# Connectors.net
KiCad netlist of a schematic drawn in Altium Designer
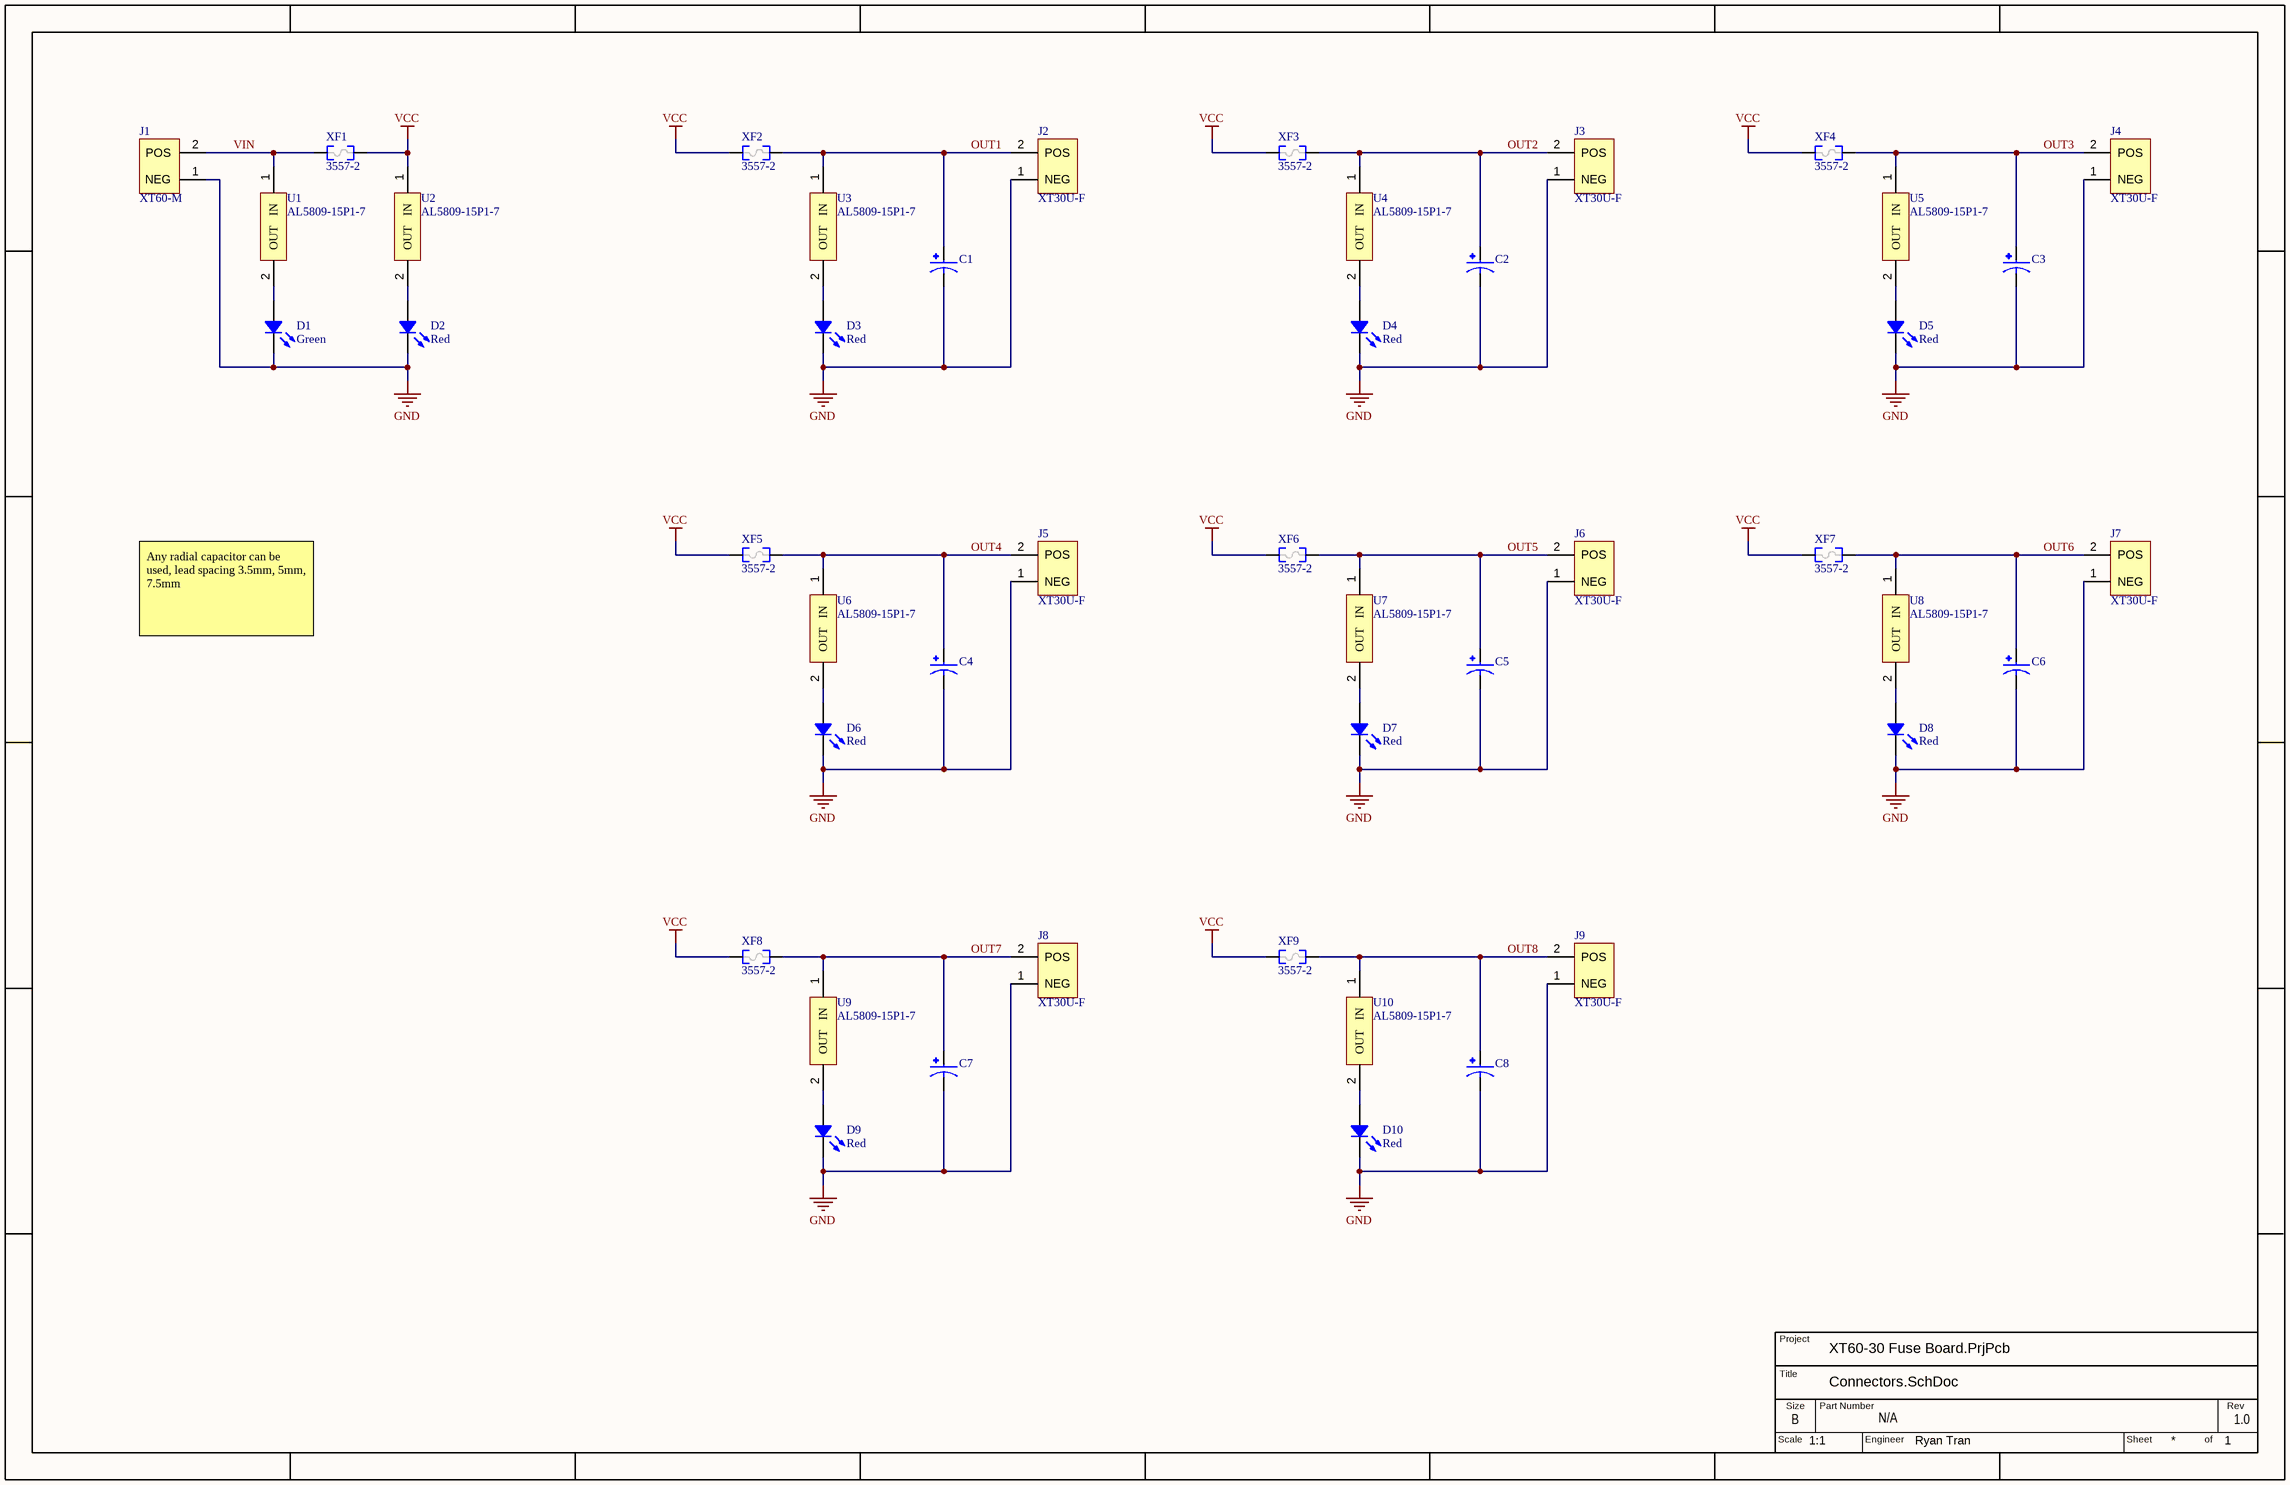
[diagram p0: Connectors.SchDoc]

(export (version "E")
  (design (tool "Eeschema 10.0.6"))
  (components
    (comp (ref "C1")
      (value "Capacitor Generic")
      (footprint "RADIAL_CAP_10mm")
      (description "Cap Radial Aluminum Cylindrical Can 3.5mm, 5mm, 7.5mm")
      (fields (field (name "MF") "Panasonic") (field (name "MP") "ECA-2WHG220"))
      (libsource (lib "XT60-30_Fuse_Board_Symbols") (part "Capacitor Generic"))
    )
    (comp (ref "C2")
      (value "Capacitor Generic")
      (footprint "RADIAL_CAP_10mm")
      (description "Cap Radial Aluminum Cylindrical Can 3.5mm, 5mm, 7.5mm")
      (fields (field (name "MF") "Panasonic") (field (name "MP") "ECA-2WHG220"))
      (libsource (lib "XT60-30_Fuse_Board_Symbols") (part "Capacitor Generic"))
    )
    (comp (ref "C3")
      (value "Capacitor Generic")
      (footprint "RADIAL_CAP_10mm")
      (description "Cap Radial Aluminum Cylindrical Can 3.5mm, 5mm, 7.5mm")
      (fields (field (name "MF") "Panasonic") (field (name "MP") "ECA-2WHG220"))
      (libsource (lib "XT60-30_Fuse_Board_Symbols") (part "Capacitor Generic"))
    )
    (comp (ref "C4")
      (value "Capacitor Generic")
      (footprint "RADIAL_CAP_10mm")
      (description "Cap Radial Aluminum Cylindrical Can 3.5mm, 5mm, 7.5mm")
      (fields (field (name "MF") "Panasonic") (field (name "MP") "ECA-2WHG220"))
      (libsource (lib "XT60-30_Fuse_Board_Symbols") (part "Capacitor Generic"))
    )
    (comp (ref "C5")
      (value "Capacitor Generic")
      (footprint "RADIAL_CAP_10mm")
      (description "Cap Radial Aluminum Cylindrical Can 3.5mm, 5mm, 7.5mm")
      (fields (field (name "MF") "Panasonic") (field (name "MP") "ECA-2WHG220"))
      (libsource (lib "XT60-30_Fuse_Board_Symbols") (part "Capacitor Generic"))
    )
    (comp (ref "C6")
      (value "Capacitor Generic")
      (footprint "RADIAL_CAP_10mm")
      (description "Cap Radial Aluminum Cylindrical Can 3.5mm, 5mm, 7.5mm")
      (fields (field (name "MF") "Panasonic") (field (name "MP") "ECA-2WHG220"))
      (libsource (lib "XT60-30_Fuse_Board_Symbols") (part "Capacitor Generic"))
    )
    (comp (ref "C7")
      (value "Capacitor Generic")
      (footprint "RADIAL_CAP_10mm")
      (description "Cap Radial Aluminum Cylindrical Can 3.5mm, 5mm, 7.5mm")
      (fields (field (name "MF") "Panasonic") (field (name "MP") "ECA-2WHG220"))
      (libsource (lib "XT60-30_Fuse_Board_Symbols") (part "Capacitor Generic"))
    )
    (comp (ref "C8")
      (value "Capacitor Generic")
      (footprint "RADIAL_CAP_10mm")
      (description "Cap Radial Aluminum Cylindrical Can 3.5mm, 5mm, 7.5mm")
      (fields (field (name "MF") "Panasonic") (field (name "MP") "ECA-2WHG220"))
      (libsource (lib "XT60-30_Fuse_Board_Symbols") (part "Capacitor Generic"))
    )
    (comp (ref "D1")
      (value "Green")
      (footprint "LED 0603_1608 GREEN")
      (description "LED GREEN CLEAR CHIP SMD")
      (fields (field (name "PART NUMBER") "LTST-C193TGKT-5A") (field (name "MANUFACTURER") "Lite-On Inc."))
      (libsource (lib "Celestial Altium Library - altium_library") (part "LED"))
    )
    (comp (ref "D2")
      (value "Red")
      (footprint "LED 0603_1608 RED")
      (description "LED RED CLEAR 2SMD")
      (fields
        (field (name "PART NUMBER") "19-217/R6C-AL1M2VY/3T")
        (field (name "MANUFACTURER") "Everlight Electronics Co Ltd")
      )
      (libsource (lib "Celestial Altium Library - altium_library") (part "LED"))
    )
    (comp (ref "D3")
      (value "Red")
      (footprint "LED 0603_1608 RED")
      (description "LED RED CLEAR 2SMD")
      (fields
        (field (name "PART NUMBER") "19-217/R6C-AL1M2VY/3T")
        (field (name "MANUFACTURER") "Everlight Electronics Co Ltd")
      )
      (libsource (lib "Celestial Altium Library - altium_library") (part "LED"))
    )
    (comp (ref "D4")
      (value "Red")
      (footprint "LED 0603_1608 RED")
      (description "LED RED CLEAR 2SMD")
      (fields
        (field (name "PART NUMBER") "19-217/R6C-AL1M2VY/3T")
        (field (name "MANUFACTURER") "Everlight Electronics Co Ltd")
      )
      (libsource (lib "Celestial Altium Library - altium_library") (part "LED"))
    )
    (comp (ref "D5")
      (value "Red")
      (footprint "LED 0603_1608 RED")
      (description "LED RED CLEAR 2SMD")
      (fields
        (field (name "PART NUMBER") "19-217/R6C-AL1M2VY/3T")
        (field (name "MANUFACTURER") "Everlight Electronics Co Ltd")
      )
      (libsource (lib "Celestial Altium Library - altium_library") (part "LED"))
    )
    (comp (ref "D6")
      (value "Red")
      (footprint "LED 0603_1608 RED")
      (description "LED RED CLEAR 2SMD")
      (fields
        (field (name "PART NUMBER") "19-217/R6C-AL1M2VY/3T")
        (field (name "MANUFACTURER") "Everlight Electronics Co Ltd")
      )
      (libsource (lib "Celestial Altium Library - altium_library") (part "LED"))
    )
    (comp (ref "D7")
      (value "Red")
      (footprint "LED 0603_1608 RED")
      (description "LED RED CLEAR 2SMD")
      (fields
        (field (name "PART NUMBER") "19-217/R6C-AL1M2VY/3T")
        (field (name "MANUFACTURER") "Everlight Electronics Co Ltd")
      )
      (libsource (lib "Celestial Altium Library - altium_library") (part "LED"))
    )
    (comp (ref "D8")
      (value "Red")
      (footprint "LED 0603_1608 RED")
      (description "LED RED CLEAR 2SMD")
      (fields
        (field (name "PART NUMBER") "19-217/R6C-AL1M2VY/3T")
        (field (name "MANUFACTURER") "Everlight Electronics Co Ltd")
      )
      (libsource (lib "Celestial Altium Library - altium_library") (part "LED"))
    )
    (comp (ref "D9")
      (value "Red")
      (footprint "LED 0603_1608 RED")
      (description "LED RED CLEAR 2SMD")
      (fields
        (field (name "PART NUMBER") "19-217/R6C-AL1M2VY/3T")
        (field (name "MANUFACTURER") "Everlight Electronics Co Ltd")
      )
      (libsource (lib "Celestial Altium Library - altium_library") (part "LED"))
    )
    (comp (ref "D10")
      (value "Red")
      (footprint "LED 0603_1608 RED")
      (description "LED RED CLEAR 2SMD")
      (fields
        (field (name "PART NUMBER") "19-217/R6C-AL1M2VY/3T")
        (field (name "MANUFACTURER") "Everlight Electronics Co Ltd")
      )
      (libsource (lib "Celestial Altium Library - altium_library") (part "LED"))
    )
    (comp (ref "J1")
      (value "XT60-M")
      (footprint "AMASS_XT60-M")
      (description "Plug; DC supply; XT60; male; PIN: 2; for cable; soldered; 30A; 500V")
      (fields (field (name "MF") "AMASS"))
      (libsource (lib "XT60-30_Fuse_Board_Symbols") (part "XT60-M"))
    )
    (comp (ref "J2")
      (value "XT30U-F")
      (footprint "AMASS_XT30-M")
      (description "Plug; DC supply; XT30; female; PIN: 2; for cable; soldering; 15A")
      (fields (field (name "MP") "XT60-M") (field (name "MF") "AMASS"))
      (libsource (lib "XT60-30_Fuse_Board_Symbols") (part "XT30U-F"))
    )
    (comp (ref "J3")
      (value "XT30U-F")
      (footprint "AMASS_XT30-M")
      (description "Plug; DC supply; XT30; female; PIN: 2; for cable; soldering; 15A")
      (fields (field (name "MP") "XT60-M") (field (name "MF") "AMASS"))
      (libsource (lib "XT60-30_Fuse_Board_Symbols") (part "XT30U-F"))
    )
    (comp (ref "J4")
      (value "XT30U-F")
      (footprint "AMASS_XT30-M")
      (description "Plug; DC supply; XT30; female; PIN: 2; for cable; soldering; 15A")
      (fields (field (name "MP") "XT60-M") (field (name "MF") "AMASS"))
      (libsource (lib "XT60-30_Fuse_Board_Symbols") (part "XT30U-F"))
    )
    (comp (ref "J5")
      (value "XT30U-F")
      (footprint "AMASS_XT30-M")
      (description "Plug; DC supply; XT30; female; PIN: 2; for cable; soldering; 15A")
      (fields (field (name "MP") "XT60-M") (field (name "MF") "AMASS"))
      (libsource (lib "XT60-30_Fuse_Board_Symbols") (part "XT30U-F"))
    )
    (comp (ref "J6")
      (value "XT30U-F")
      (footprint "AMASS_XT30-M")
      (description "Plug; DC supply; XT30; female; PIN: 2; for cable; soldering; 15A")
      (fields (field (name "MP") "XT60-M") (field (name "MF") "AMASS"))
      (libsource (lib "XT60-30_Fuse_Board_Symbols") (part "XT30U-F"))
    )
    (comp (ref "J7")
      (value "XT30U-F")
      (footprint "AMASS_XT30-M")
      (description "Plug; DC supply; XT30; female; PIN: 2; for cable; soldering; 15A")
      (fields (field (name "MP") "XT60-M") (field (name "MF") "AMASS"))
      (libsource (lib "XT60-30_Fuse_Board_Symbols") (part "XT30U-F"))
    )
    (comp (ref "J8")
      (value "XT30U-F")
      (footprint "AMASS_XT30-M")
      (description "Plug; DC supply; XT30; female; PIN: 2; for cable; soldering; 15A")
      (fields (field (name "MP") "XT60-M") (field (name "MF") "AMASS"))
      (libsource (lib "XT60-30_Fuse_Board_Symbols") (part "XT30U-F"))
    )
    (comp (ref "J9")
      (value "XT30U-F")
      (footprint "AMASS_XT30-M")
      (description "Plug; DC supply; XT30; female; PIN: 2; for cable; soldering; 15A")
      (fields (field (name "MP") "XT60-M") (field (name "MF") "AMASS"))
      (libsource (lib "XT60-30_Fuse_Board_Symbols") (part "XT30U-F"))
    )
    (comp (ref "U1")
      (value "AL5809-15P1-7")
      (footprint "DIOD-POWERDI123-2_B_V")
      (description "Constant Current LED Driver, 2.5 to 60 V, -40 to 125 degC, 2-Pin SMD, RoHS, Tape and Reel")
      (libsource (lib "Altium Content Vault") (part "DIOD-AL5809-2"))
    )
    (comp (ref "U2")
      (value "AL5809-15P1-7")
      (footprint "DIOD-POWERDI123-2_B_V")
      (description "Constant Current LED Driver, 2.5 to 60 V, -40 to 125 degC, 2-Pin SMD, RoHS, Tape and Reel")
      (libsource (lib "Altium Content Vault") (part "DIOD-AL5809-2"))
    )
    (comp (ref "U3")
      (value "AL5809-15P1-7")
      (footprint "DIOD-POWERDI123-2_B_V")
      (description "Constant Current LED Driver, 2.5 to 60 V, -40 to 125 degC, 2-Pin SMD, RoHS, Tape and Reel")
      (libsource (lib "Altium Content Vault") (part "DIOD-AL5809-2"))
    )
    (comp (ref "U4")
      (value "AL5809-15P1-7")
      (footprint "DIOD-POWERDI123-2_B_V")
      (description "Constant Current LED Driver, 2.5 to 60 V, -40 to 125 degC, 2-Pin SMD, RoHS, Tape and Reel")
      (libsource (lib "Altium Content Vault") (part "DIOD-AL5809-2"))
    )
    (comp (ref "U5")
      (value "AL5809-15P1-7")
      (footprint "DIOD-POWERDI123-2_B_V")
      (description "Constant Current LED Driver, 2.5 to 60 V, -40 to 125 degC, 2-Pin SMD, RoHS, Tape and Reel")
      (libsource (lib "Altium Content Vault") (part "DIOD-AL5809-2"))
    )
    (comp (ref "U6")
      (value "AL5809-15P1-7")
      (footprint "DIOD-POWERDI123-2_B_V")
      (description "Constant Current LED Driver, 2.5 to 60 V, -40 to 125 degC, 2-Pin SMD, RoHS, Tape and Reel")
      (libsource (lib "Altium Content Vault") (part "DIOD-AL5809-2"))
    )
    (comp (ref "U7")
      (value "AL5809-15P1-7")
      (footprint "DIOD-POWERDI123-2_B_V")
      (description "Constant Current LED Driver, 2.5 to 60 V, -40 to 125 degC, 2-Pin SMD, RoHS, Tape and Reel")
      (libsource (lib "Altium Content Vault") (part "DIOD-AL5809-2"))
    )
    (comp (ref "U8")
      (value "AL5809-15P1-7")
      (footprint "DIOD-POWERDI123-2_B_V")
      (description "Constant Current LED Driver, 2.5 to 60 V, -40 to 125 degC, 2-Pin SMD, RoHS, Tape and Reel")
      (libsource (lib "Altium Content Vault") (part "DIOD-AL5809-2"))
    )
    (comp (ref "U9")
      (value "AL5809-15P1-7")
      (footprint "DIOD-POWERDI123-2_B_V")
      (description "Constant Current LED Driver, 2.5 to 60 V, -40 to 125 degC, 2-Pin SMD, RoHS, Tape and Reel")
      (libsource (lib "Altium Content Vault") (part "DIOD-AL5809-2"))
    )
    (comp (ref "U10")
      (value "AL5809-15P1-7")
      (footprint "DIOD-POWERDI123-2_B_V")
      (description "Constant Current LED Driver, 2.5 to 60 V, -40 to 125 degC, 2-Pin SMD, RoHS, Tape and Reel")
      (libsource (lib "Altium Content Vault") (part "DIOD-AL5809-2"))
    )
    (comp (ref "XF1")
      (value "3557-2")
      (footprint "FUSE_3557-2")
      (description "Fuse Block 30A 500V 1 Circuit Blade Through Hole")
      (fields (field (name "MF") "Keystone Electronics"))
      (libsource (lib "XT60-30_Fuse_Board_Symbols") (part "3557-2"))
    )
    (comp (ref "XF2")
      (value "3557-2")
      (footprint "FUSE_3557-2")
      (description "Fuse Block 30A 500V 1 Circuit Blade Through Hole")
      (fields (field (name "MF") "Keystone Electronics"))
      (libsource (lib "XT60-30_Fuse_Board_Symbols") (part "3557-2"))
    )
    (comp (ref "XF3")
      (value "3557-2")
      (footprint "FUSE_3557-2")
      (description "Fuse Block 30A 500V 1 Circuit Blade Through Hole")
      (fields (field (name "MF") "Keystone Electronics"))
      (libsource (lib "XT60-30_Fuse_Board_Symbols") (part "3557-2"))
    )
    (comp (ref "XF4")
      (value "3557-2")
      (footprint "FUSE_3557-2")
      (description "Fuse Block 30A 500V 1 Circuit Blade Through Hole")
      (fields (field (name "MF") "Keystone Electronics"))
      (libsource (lib "XT60-30_Fuse_Board_Symbols") (part "3557-2"))
    )
    (comp (ref "XF5")
      (value "3557-2")
      (footprint "FUSE_3557-2")
      (description "Fuse Block 30A 500V 1 Circuit Blade Through Hole")
      (fields (field (name "MF") "Keystone Electronics"))
      (libsource (lib "XT60-30_Fuse_Board_Symbols") (part "3557-2"))
    )
    (comp (ref "XF6")
      (value "3557-2")
      (footprint "FUSE_3557-2")
      (description "Fuse Block 30A 500V 1 Circuit Blade Through Hole")
      (fields (field (name "MF") "Keystone Electronics"))
      (libsource (lib "XT60-30_Fuse_Board_Symbols") (part "3557-2"))
    )
    (comp (ref "XF7")
      (value "3557-2")
      (footprint "FUSE_3557-2")
      (description "Fuse Block 30A 500V 1 Circuit Blade Through Hole")
      (fields (field (name "MF") "Keystone Electronics"))
      (libsource (lib "XT60-30_Fuse_Board_Symbols") (part "3557-2"))
    )
    (comp (ref "XF8")
      (value "3557-2")
      (footprint "FUSE_3557-2")
      (description "Fuse Block 30A 500V 1 Circuit Blade Through Hole")
      (fields (field (name "MF") "Keystone Electronics"))
      (libsource (lib "XT60-30_Fuse_Board_Symbols") (part "3557-2"))
    )
    (comp (ref "XF9")
      (value "3557-2")
      (footprint "FUSE_3557-2")
      (description "Fuse Block 30A 500V 1 Circuit Blade Through Hole")
      (fields (field (name "MF") "Keystone Electronics"))
      (libsource (lib "XT60-30_Fuse_Board_Symbols") (part "3557-2"))
    )
  )
  (nets
    (net (code "1") (name "/OUT1") (class "Default")
      (node (ref "C1") (pin "2") (pinfunction "2_2") (pintype "passive"))
      (node (ref "J2") (pin "2") (pinfunction "POS_2") (pintype "passive"))
      (node (ref "U3") (pin "1") (pinfunction "IN_1") (pintype "passive"))
      (node (ref "XF2") (pin "2") (pinfunction "2_2") (pintype "passive"))
    )
    (net (code "2") (name "/OUT2") (class "Default")
      (node (ref "C2") (pin "2") (pinfunction "2_2") (pintype "passive"))
      (node (ref "J3") (pin "2") (pinfunction "POS_2") (pintype "passive"))
      (node (ref "U4") (pin "1") (pinfunction "IN_1") (pintype "passive"))
      (node (ref "XF3") (pin "2") (pinfunction "2_2") (pintype "passive"))
    )
    (net (code "3") (name "/OUT3") (class "Default")
      (node (ref "C3") (pin "2") (pinfunction "2_2") (pintype "passive"))
      (node (ref "J4") (pin "2") (pinfunction "POS_2") (pintype "passive"))
      (node (ref "U5") (pin "1") (pinfunction "IN_1") (pintype "passive"))
      (node (ref "XF4") (pin "2") (pinfunction "2_2") (pintype "passive"))
    )
    (net (code "4") (name "/OUT4") (class "Default")
      (node (ref "C4") (pin "2") (pinfunction "2_2") (pintype "passive"))
      (node (ref "J5") (pin "2") (pinfunction "POS_2") (pintype "passive"))
      (node (ref "U6") (pin "1") (pinfunction "IN_1") (pintype "passive"))
      (node (ref "XF5") (pin "2") (pinfunction "2_2") (pintype "passive"))
    )
    (net (code "5") (name "/OUT5") (class "Default")
      (node (ref "C5") (pin "2") (pinfunction "2_2") (pintype "passive"))
      (node (ref "J6") (pin "2") (pinfunction "POS_2") (pintype "passive"))
      (node (ref "U7") (pin "1") (pinfunction "IN_1") (pintype "passive"))
      (node (ref "XF6") (pin "2") (pinfunction "2_2") (pintype "passive"))
    )
    (net (code "6") (name "/OUT6") (class "Default")
      (node (ref "C6") (pin "2") (pinfunction "2_2") (pintype "passive"))
      (node (ref "J7") (pin "2") (pinfunction "POS_2") (pintype "passive"))
      (node (ref "U8") (pin "1") (pinfunction "IN_1") (pintype "passive"))
      (node (ref "XF7") (pin "2") (pinfunction "2_2") (pintype "passive"))
    )
    (net (code "7") (name "/OUT7") (class "Default")
      (node (ref "C7") (pin "2") (pinfunction "2_2") (pintype "passive"))
      (node (ref "J8") (pin "2") (pinfunction "POS_2") (pintype "passive"))
      (node (ref "U9") (pin "1") (pinfunction "IN_1") (pintype "passive"))
      (node (ref "XF8") (pin "2") (pinfunction "2_2") (pintype "passive"))
    )
    (net (code "8") (name "/OUT8") (class "Default")
      (node (ref "C8") (pin "2") (pinfunction "2_2") (pintype "passive"))
      (node (ref "J9") (pin "2") (pinfunction "POS_2") (pintype "passive"))
      (node (ref "U10") (pin "1") (pinfunction "IN_1") (pintype "passive"))
      (node (ref "XF9") (pin "2") (pinfunction "2_2") (pintype "passive"))
    )
    (net (code "9") (name "/VIN") (class "Default")
      (node (ref "J1") (pin "2") (pinfunction "POS_2") (pintype "passive"))
      (node (ref "U1") (pin "1") (pinfunction "IN_1") (pintype "passive"))
      (node (ref "XF1") (pin "1") (pinfunction "1_1") (pintype "passive"))
    )
    (net (code "10") (name "GND") (class "Default")
      (node (ref "C1") (pin "1") (pinfunction "1_1") (pintype "passive"))
      (node (ref "C2") (pin "1") (pinfunction "1_1") (pintype "passive"))
      (node (ref "C3") (pin "1") (pinfunction "1_1") (pintype "passive"))
      (node (ref "C4") (pin "1") (pinfunction "1_1") (pintype "passive"))
      (node (ref "C5") (pin "1") (pinfunction "1_1") (pintype "passive"))
      (node (ref "C6") (pin "1") (pinfunction "1_1") (pintype "passive"))
      (node (ref "C7") (pin "1") (pinfunction "1_1") (pintype "passive"))
      (node (ref "C8") (pin "1") (pinfunction "1_1") (pintype "passive"))
      (node (ref "D1") (pin "2") (pinfunction "2_2") (pintype "passive"))
      (node (ref "D10") (pin "2") (pinfunction "2_2") (pintype "passive"))
      (node (ref "D2") (pin "2") (pinfunction "2_2") (pintype "passive"))
      (node (ref "D3") (pin "2") (pinfunction "2_2") (pintype "passive"))
      (node (ref "D4") (pin "2") (pinfunction "2_2") (pintype "passive"))
      (node (ref "D5") (pin "2") (pinfunction "2_2") (pintype "passive"))
      (node (ref "D6") (pin "2") (pinfunction "2_2") (pintype "passive"))
      (node (ref "D7") (pin "2") (pinfunction "2_2") (pintype "passive"))
      (node (ref "D8") (pin "2") (pinfunction "2_2") (pintype "passive"))
      (node (ref "D9") (pin "2") (pinfunction "2_2") (pintype "passive"))
      (node (ref "J1") (pin "1") (pinfunction "NEG_1") (pintype "passive"))
      (node (ref "J2") (pin "1") (pinfunction "NEG_1") (pintype "passive"))
      (node (ref "J3") (pin "1") (pinfunction "NEG_1") (pintype "passive"))
      (node (ref "J4") (pin "1") (pinfunction "NEG_1") (pintype "passive"))
      (node (ref "J5") (pin "1") (pinfunction "NEG_1") (pintype "passive"))
      (node (ref "J6") (pin "1") (pinfunction "NEG_1") (pintype "passive"))
      (node (ref "J7") (pin "1") (pinfunction "NEG_1") (pintype "passive"))
      (node (ref "J8") (pin "1") (pinfunction "NEG_1") (pintype "passive"))
      (node (ref "J9") (pin "1") (pinfunction "NEG_1") (pintype "passive"))
    )
    (net (code "11") (name "Net-(U1-OUT)") (class "Default")
      (node (ref "D1") (pin "1") (pinfunction "1_1") (pintype "passive"))
      (node (ref "U1") (pin "2") (pinfunction "OUT_2") (pintype "passive"))
    )
    (net (code "12") (name "Net-(U2-OUT)") (class "Default")
      (node (ref "D2") (pin "1") (pinfunction "1_1") (pintype "passive"))
      (node (ref "U2") (pin "2") (pinfunction "OUT_2") (pintype "passive"))
    )
    (net (code "13") (name "Net-(U3-OUT)") (class "Default")
      (node (ref "D3") (pin "1") (pinfunction "1_1") (pintype "passive"))
      (node (ref "U3") (pin "2") (pinfunction "OUT_2") (pintype "passive"))
    )
    (net (code "14") (name "Net-(U4-OUT)") (class "Default")
      (node (ref "D4") (pin "1") (pinfunction "1_1") (pintype "passive"))
      (node (ref "U4") (pin "2") (pinfunction "OUT_2") (pintype "passive"))
    )
    (net (code "15") (name "Net-(U5-OUT)") (class "Default")
      (node (ref "D5") (pin "1") (pinfunction "1_1") (pintype "passive"))
      (node (ref "U5") (pin "2") (pinfunction "OUT_2") (pintype "passive"))
    )
    (net (code "16") (name "Net-(U6-OUT)") (class "Default")
      (node (ref "D6") (pin "1") (pinfunction "1_1") (pintype "passive"))
      (node (ref "U6") (pin "2") (pinfunction "OUT_2") (pintype "passive"))
    )
    (net (code "17") (name "Net-(U7-OUT)") (class "Default")
      (node (ref "D7") (pin "1") (pinfunction "1_1") (pintype "passive"))
      (node (ref "U7") (pin "2") (pinfunction "OUT_2") (pintype "passive"))
    )
    (net (code "18") (name "Net-(U8-OUT)") (class "Default")
      (node (ref "D8") (pin "1") (pinfunction "1_1") (pintype "passive"))
      (node (ref "U8") (pin "2") (pinfunction "OUT_2") (pintype "passive"))
    )
    (net (code "19") (name "Net-(U9-OUT)") (class "Default")
      (node (ref "D9") (pin "1") (pinfunction "1_1") (pintype "passive"))
      (node (ref "U9") (pin "2") (pinfunction "OUT_2") (pintype "passive"))
    )
    (net (code "20") (name "Net-(U10-OUT)") (class "Default")
      (node (ref "D10") (pin "1") (pinfunction "1_1") (pintype "passive"))
      (node (ref "U10") (pin "2") (pinfunction "OUT_2") (pintype "passive"))
    )
    (net (code "21") (name "VCC") (class "Default")
      (node (ref "U2") (pin "1") (pinfunction "IN_1") (pintype "passive"))
      (node (ref "XF1") (pin "2") (pinfunction "2_2") (pintype "passive"))
      (node (ref "XF2") (pin "1") (pinfunction "1_1") (pintype "passive"))
      (node (ref "XF3") (pin "1") (pinfunction "1_1") (pintype "passive"))
      (node (ref "XF4") (pin "1") (pinfunction "1_1") (pintype "passive"))
      (node (ref "XF5") (pin "1") (pinfunction "1_1") (pintype "passive"))
      (node (ref "XF6") (pin "1") (pinfunction "1_1") (pintype "passive"))
      (node (ref "XF7") (pin "1") (pinfunction "1_1") (pintype "passive"))
      (node (ref "XF8") (pin "1") (pinfunction "1_1") (pintype "passive"))
      (node (ref "XF9") (pin "1") (pinfunction "1_1") (pintype "passive"))
    )
  )
)
